# eclet.net
KiCad netlist of a schematic drawn in EAGLE
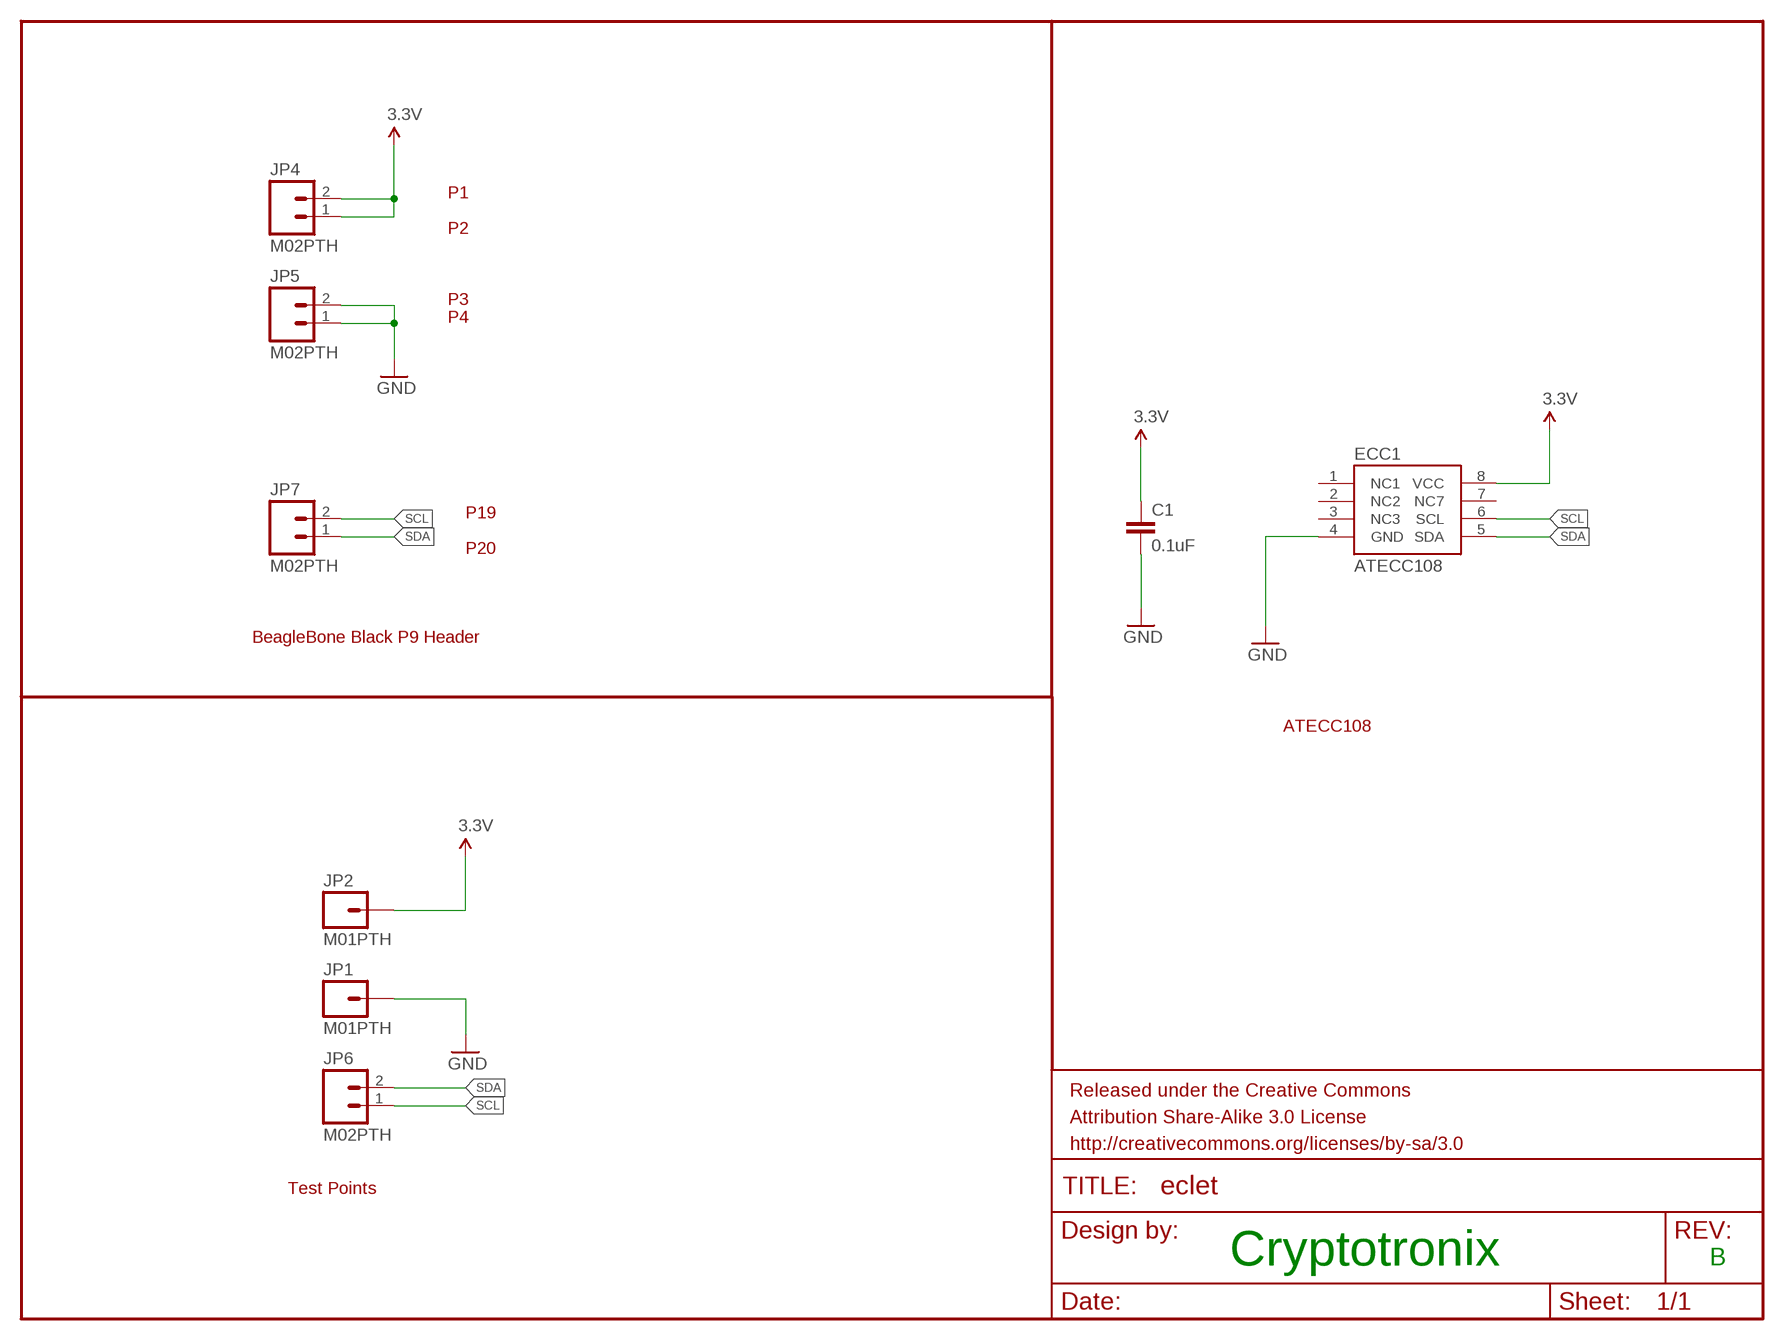
[diagram p0: schematic, sheet 1]

(export (version "E")
  (design (tool "Eeschema 10.0.6"))
  (components
    (comp (ref "C1")
      (value "0.1uF")
      (footprint "eagle-import:0603-CAP")
      (libsource (lib "eagle-import") (part "0.1UF-100V-10%(0603)"))
    )
    (comp (ref "ECC1")
      (value "ATECC108")
      (footprint "eagle-import:SOIC8")
      (libsource (lib "eagle-import") (part "ATECC108"))
    )
    (comp (ref "FRAME1")
      (value "FRAME-LETTER")
      (footprint "eagle-import:CREATIVE_COMMONS")
      (libsource (lib "eagle-import") (part "FRAME-LETTER"))
    )
    (comp (ref "JP1")
      (value "M01PTH")
      (footprint "eagle-import:1X01")
      (libsource (lib "eagle-import") (part "M01PTH"))
    )
    (comp (ref "JP2")
      (value "M01PTH")
      (footprint "eagle-import:1X01")
      (libsource (lib "eagle-import") (part "M01PTH"))
    )
    (comp (ref "JP4")
      (value "M02PTH")
      (footprint "eagle-import:1X02")
      (libsource (lib "eagle-import") (part "M02PTH"))
    )
    (comp (ref "JP5")
      (value "M02PTH")
      (footprint "eagle-import:1X02")
      (libsource (lib "eagle-import") (part "M02PTH"))
    )
    (comp (ref "JP6")
      (value "M02PTH")
      (footprint "eagle-import:1X02")
      (libsource (lib "eagle-import") (part "M02PTH"))
    )
    (comp (ref "JP7")
      (value "M02PTH")
      (footprint "eagle-import:1X02")
      (libsource (lib "eagle-import") (part "M02PTH"))
    )
  )
  (nets
    (net (code "1") (name "3.3V") (class "Default")
      (node (ref "C1") (pin "1") (pinfunction "1_1") (pintype "passive"))
      (node (ref "ECC1") (pin "8") (pinfunction "VCC_8") (pintype "power_in"))
      (node (ref "JP2") (pin "1") (pinfunction "1_1") (pintype "passive"))
      (node (ref "JP4") (pin "1") (pinfunction "1_1") (pintype "passive"))
      (node (ref "JP4") (pin "2") (pinfunction "2_2") (pintype "passive"))
    )
    (net (code "2") (name "GND") (class "Default")
      (node (ref "C1") (pin "2") (pinfunction "2_2") (pintype "passive"))
      (node (ref "ECC1") (pin "4") (pinfunction "GND_4") (pintype "power_in"))
      (node (ref "JP1") (pin "1") (pinfunction "1_1") (pintype "passive"))
      (node (ref "JP5") (pin "1") (pinfunction "1_1") (pintype "passive"))
      (node (ref "JP5") (pin "2") (pinfunction "2_2") (pintype "passive"))
    )
    (net (code "3") (name "SCL") (class "Default")
      (node (ref "ECC1") (pin "6") (pinfunction "SCL_6") (pintype "bidirectional"))
      (node (ref "JP6") (pin "1") (pinfunction "1_1") (pintype "passive"))
      (node (ref "JP7") (pin "2") (pinfunction "2_2") (pintype "passive"))
    )
    (net (code "4") (name "SDA") (class "Default")
      (node (ref "ECC1") (pin "5") (pinfunction "SDA_5") (pintype "bidirectional"))
      (node (ref "JP6") (pin "2") (pinfunction "2_2") (pintype "passive"))
      (node (ref "JP7") (pin "1") (pinfunction "1_1") (pintype "passive"))
    )
    (net (code "5") (name "unconnected-(ECC1-NC1-Pad1)") (class "Default")
      (node (ref "ECC1") (pin "1") (pinfunction "NC1_1") (pintype "bidirectional"))
    )
    (net (code "6") (name "unconnected-(ECC1-NC2-Pad2)") (class "Default")
      (node (ref "ECC1") (pin "2") (pinfunction "NC2_2") (pintype "no_connect"))
    )
    (net (code "7") (name "unconnected-(ECC1-NC3-Pad3)") (class "Default")
      (node (ref "ECC1") (pin "3") (pinfunction "NC3_3") (pintype "no_connect"))
    )
    (net (code "8") (name "unconnected-(ECC1-NC7-Pad7)") (class "Default")
      (node (ref "ECC1") (pin "7") (pinfunction "NC7_7") (pintype "no_connect"))
    )
  )
)
